# lightspeakers.net
KiCad netlist of a schematic drawn in EAGLE
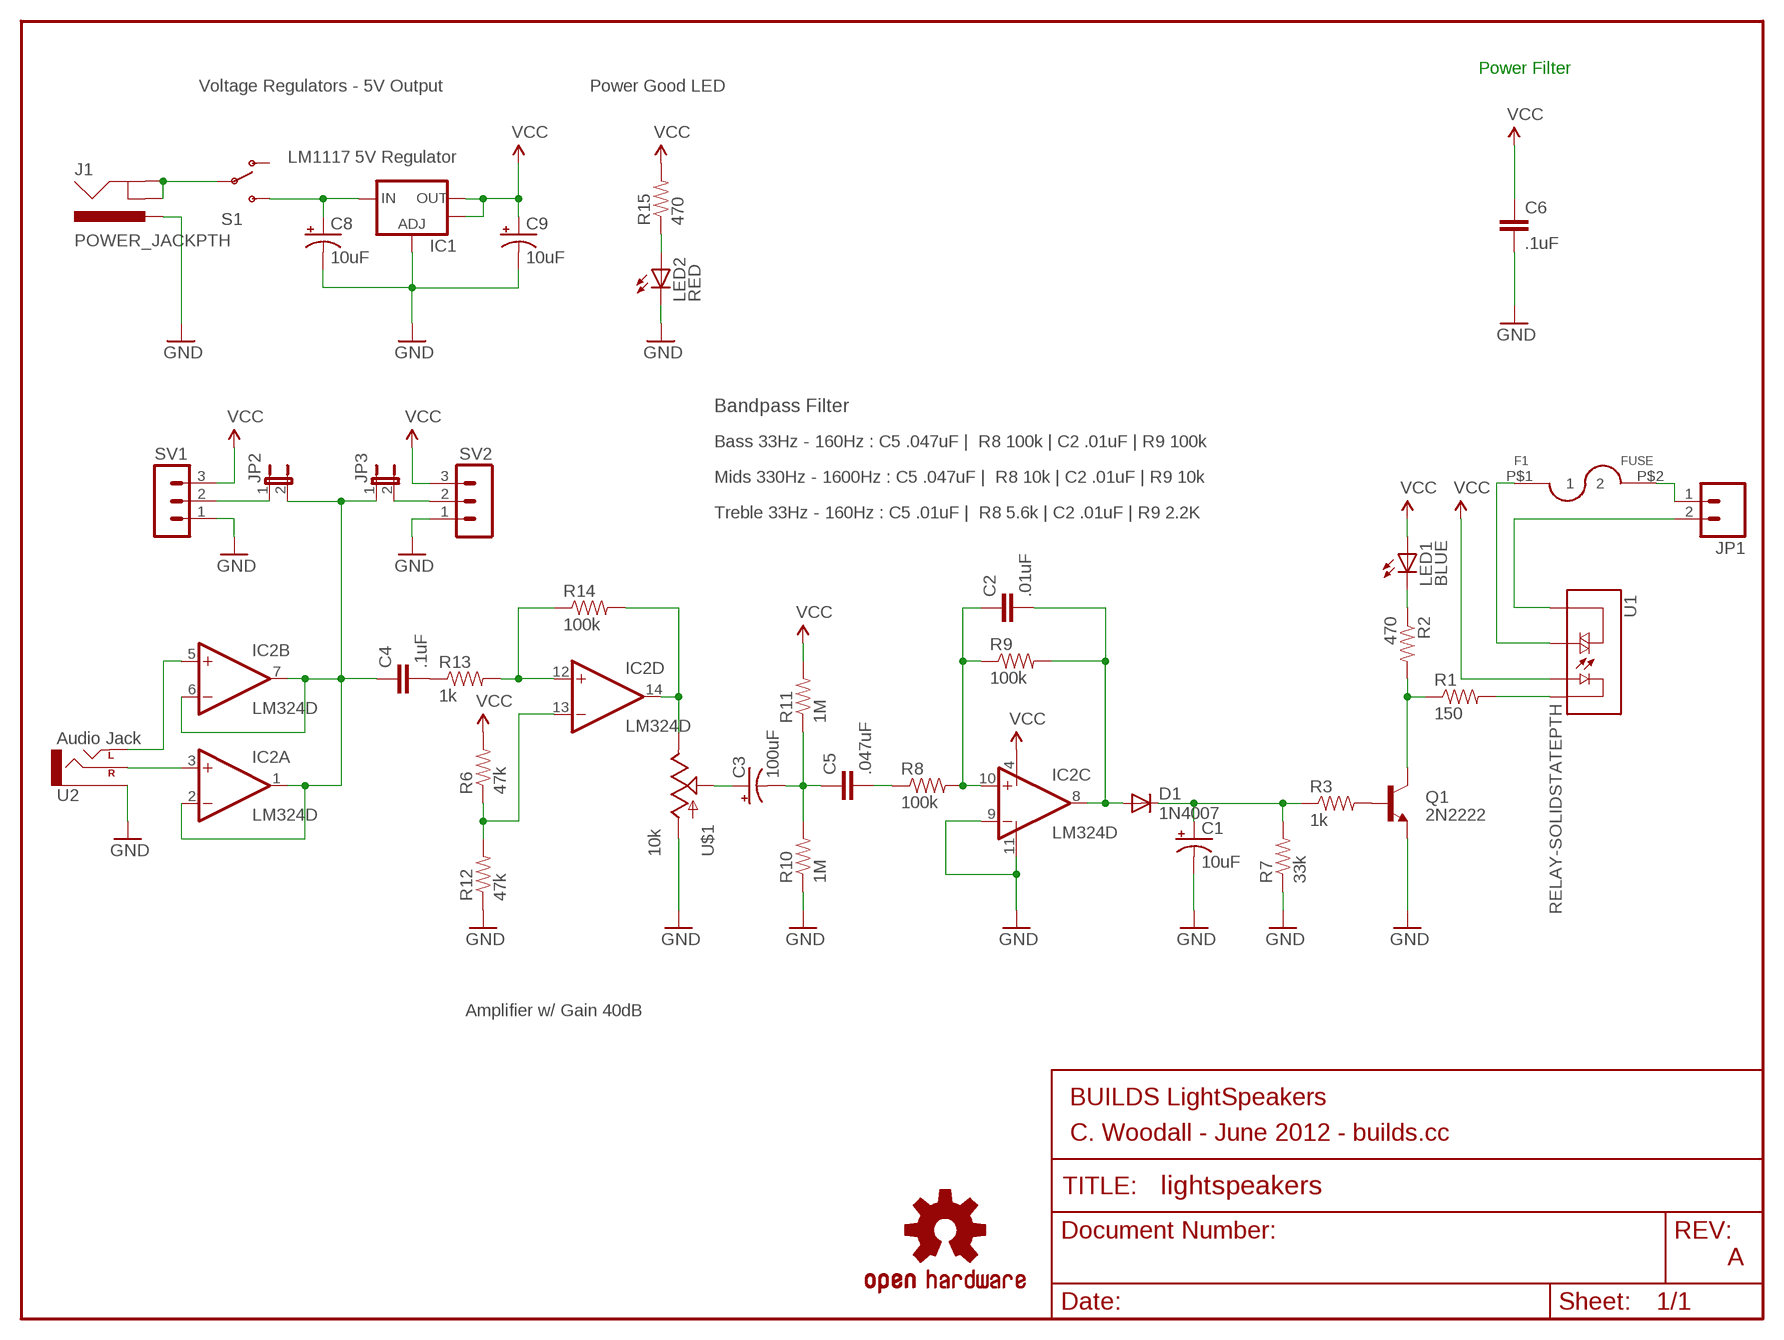
[diagram p0: schematic, sheet 1]

(export (version "E")
  (design (tool "Eeschema 10.0.6"))
  (components
    (comp (ref "C1")
      (value "10uF")
      (footprint "eagle-import:CPOL-RADIAL-10UF-25V")
      (libsource (lib "eagle-import") (part "CAP_POLPTH2"))
    )
    (comp (ref "C2")
      (value ".01uF")
      (footprint "eagle-import:0603-CAP")
      (libsource (lib "eagle-import") (part "CAP0603-CAP"))
    )
    (comp (ref "C3")
      (value "100uF")
      (footprint "eagle-import:CPOL-RADIAL-100UF-25V")
      (libsource (lib "eagle-import") (part "CAP_POLPTH1"))
    )
    (comp (ref "C4")
      (value ".1uF")
      (footprint "eagle-import:0603-CAP")
      (libsource (lib "eagle-import") (part "CAP0603-CAP"))
    )
    (comp (ref "C5")
      (value ".047uF")
      (footprint "eagle-import:0603-CAP")
      (libsource (lib "eagle-import") (part "CAP0603-CAP"))
    )
    (comp (ref "C6")
      (value ".1uF")
      (footprint "eagle-import:0603-CAP")
      (libsource (lib "eagle-import") (part "CAP0603-CAP"))
    )
    (comp (ref "C8")
      (value "10uF")
      (footprint "eagle-import:CPOL-RADIAL-10UF-25V")
      (libsource (lib "eagle-import") (part "CAP_POLPTH2"))
    )
    (comp (ref "C9")
      (value "10uF")
      (footprint "eagle-import:CPOL-RADIAL-10UF-25V")
      (libsource (lib "eagle-import") (part "CAP_POLPTH2"))
    )
    (comp (ref "D1")
      (value "1N4007")
      (footprint "eagle-import:DIODE-1N4001")
      (libsource (lib "eagle-import") (part "DIODEPTH"))
    )
    (comp (ref "F1")
      (value "FUSE")
      (footprint "eagle-import:20MMX5MMFUSE")
      (libsource (lib "eagle-import") (part "FUSE"))
    )
    (comp (ref "IC1")
      (value "LM1117 5V Regulator")
      (footprint "eagle-import:SOT223")
      (libsource (lib "eagle-import") (part "V_REG_LM1117SOT223"))
    )
    (comp (ref "IC2")
      (value "LM324D")
      (footprint "eagle-import:SO14")
      (libsource (lib "eagle-import") (part "LM324D"))
    )
    (comp (ref "J1")
      (value "POWER_JACKPTH")
      (footprint "eagle-import:POWER_JACK_PTH")
      (libsource (lib "eagle-import") (part "POWER_JACKPTH"))
    )
    (comp (ref "JP1")
      (value "M025MM")
      (footprint "eagle-import:SCREWTERMINAL-5MM-2")
      (libsource (lib "eagle-import") (part "M025MM"))
    )
    (comp (ref "JP2")
      (value "JUMPER-2PTH")
      (footprint "eagle-import:1X02")
      (libsource (lib "eagle-import") (part "JUMPER-2PTH"))
    )
    (comp (ref "JP3")
      (value "JUMPER-2PTH")
      (footprint "eagle-import:1X02")
      (libsource (lib "eagle-import") (part "JUMPER-2PTH"))
    )
    (comp (ref "LED1")
      (value "BLUE")
      (footprint "eagle-import:LED-0603")
      (libsource (lib "eagle-import") (part "LED0603"))
    )
    (comp (ref "LED2")
      (value "RED")
      (footprint "eagle-import:LED-0603")
      (libsource (lib "eagle-import") (part "LED0603"))
    )
    (comp (ref "Q1")
      (value "2N2222")
      (footprint "eagle-import:TO-92-AMMO")
      (libsource (lib "eagle-import") (part "TRANSISTOR_NPNTO-92-AMMO"))
    )
    (comp (ref "R1")
      (value "150")
      (footprint "eagle-import:0603-RES")
      (libsource (lib "eagle-import") (part "RESISTOR0603-RES"))
    )
    (comp (ref "R2")
      (value "470")
      (footprint "eagle-import:0603-RES")
      (libsource (lib "eagle-import") (part "RESISTOR0603-RES"))
    )
    (comp (ref "R3")
      (value "1k")
      (footprint "eagle-import:0603-RES")
      (libsource (lib "eagle-import") (part "RESISTOR0603-RES"))
    )
    (comp (ref "R6")
      (value "47k")
      (footprint "eagle-import:0603-RES")
      (libsource (lib "eagle-import") (part "RESISTOR0603-RES"))
    )
    (comp (ref "R7")
      (value "33k")
      (footprint "eagle-import:0603-RES")
      (libsource (lib "eagle-import") (part "RESISTOR0603-RES"))
    )
    (comp (ref "R8")
      (value "100k")
      (footprint "eagle-import:0603-RES")
      (libsource (lib "eagle-import") (part "RESISTOR0603-RES"))
    )
    (comp (ref "R9")
      (value "100k")
      (footprint "eagle-import:0603-RES")
      (libsource (lib "eagle-import") (part "RESISTOR0603-RES"))
    )
    (comp (ref "R10")
      (value "1M")
      (footprint "eagle-import:0603-RES")
      (libsource (lib "eagle-import") (part "RESISTOR0603-RES"))
    )
    (comp (ref "R11")
      (value "1M")
      (footprint "eagle-import:0603-RES")
      (libsource (lib "eagle-import") (part "RESISTOR0603-RES"))
    )
    (comp (ref "R12")
      (value "47k")
      (footprint "eagle-import:0603-RES")
      (libsource (lib "eagle-import") (part "RESISTOR0603-RES"))
    )
    (comp (ref "R13")
      (value "1k")
      (footprint "eagle-import:0603-RES")
      (libsource (lib "eagle-import") (part "RESISTOR0603-RES"))
    )
    (comp (ref "R14")
      (value "100k")
      (footprint "eagle-import:0603-RES")
      (libsource (lib "eagle-import") (part "RESISTOR0603-RES"))
    )
    (comp (ref "R15")
      (value "470")
      (footprint "eagle-import:0603-RES")
      (libsource (lib "eagle-import") (part "RESISTOR0603-RES"))
    )
    (comp (ref "S1")
      (value "SWITCH-SPSTPTH")
      (footprint "eagle-import:SWITCH-SPDT")
      (libsource (lib "eagle-import") (part "SWITCH-SPSTPTH"))
    )
    (comp (ref "SV1")
      (value "MA03-1")
      (footprint "eagle-import:MA03-1")
      (libsource (lib "eagle-import") (part "MA03-1"))
    )
    (comp (ref "SV2")
      (value "MA03-1")
      (footprint "eagle-import:MA03-1")
      (libsource (lib "eagle-import") (part "MA03-1"))
    )
    (comp (ref "U$1")
      (value "10k")
      (footprint "eagle-import:3362U")
      (libsource (lib "eagle-import") (part "POT100K_3362U"))
    )
    (comp (ref "U$2")
      (value "OSHW-LOGOS")
      (footprint "eagle-import:OSHW-LOGO-S")
      (libsource (lib "eagle-import") (part "OSHW-LOGOS"))
    )
    (comp (ref "U1")
      (value "RELAY-SOLIDSTATEPTH")
      (footprint "eagle-import:RELAY-S108T02")
      (libsource (lib "eagle-import") (part "RELAY-SOLIDSTATEPTH"))
    )
    (comp (ref "U2")
      (value "Audio Jack")
      (footprint "eagle-import:AUDIO-JACK")
      (libsource (lib "eagle-import") (part "AUDIO-JACKPTH"))
    )
  )
  (nets
    (net (code "1") (name "GND") (class "Default")
      (node (ref "C1") (pin "2") (pinfunction "-_2") (pintype "passive"))
      (node (ref "C6") (pin "2") (pinfunction "2_2") (pintype "passive"))
      (node (ref "C8") (pin "2") (pinfunction "-_2") (pintype "passive"))
      (node (ref "C9") (pin "2") (pinfunction "-_2") (pintype "passive"))
      (node (ref "IC1") (pin "1") (pinfunction "ADJ_1") (pintype "input"))
      (node (ref "IC2") (pin "11") (pinfunction "V-_11") (pintype "power_in"))
      (node (ref "IC2") (pin "9") (pinfunction "-IN_9") (pintype "input"))
      (node (ref "J1") (pin "PWR") (pinfunction "PWR_PWR") (pintype "bidirectional"))
      (node (ref "LED2") (pin "C") (pinfunction "C_C") (pintype "passive"))
      (node (ref "Q1") (pin "1") (pinfunction "E_1") (pintype "passive"))
      (node (ref "R10") (pin "1") (pinfunction "1_1") (pintype "passive"))
      (node (ref "R12") (pin "1") (pinfunction "1_1") (pintype "passive"))
      (node (ref "R7") (pin "1") (pinfunction "1_1") (pintype "passive"))
      (node (ref "SV1") (pin "1") (pinfunction "1_1") (pintype "passive"))
      (node (ref "SV2") (pin "1") (pinfunction "1_1") (pintype "passive"))
      (node (ref "U$1") (pin "P$3") (pinfunction "A_P$3") (pintype "passive"))
      (node (ref "U2") (pin "SLEEVE") (pinfunction "SLEEVE_SLEEVE") (pintype "bidirectional"))
    )
    (net (code "2") (name "Net-(C1-+)") (class "Default")
      (node (ref "C1") (pin "1") (pinfunction "+_1") (pintype "passive"))
      (node (ref "D1") (pin "C") (pinfunction "C_C") (pintype "passive"))
      (node (ref "R3") (pin "1") (pinfunction "1_1") (pintype "passive"))
      (node (ref "R7") (pin "2") (pinfunction "2_2") (pintype "passive"))
    )
    (net (code "3") (name "Net-(C3-+)") (class "Default")
      (node (ref "C3") (pin "1") (pinfunction "+_1") (pintype "passive"))
      (node (ref "U$1") (pin "P$2") (pinfunction "S_P$2") (pintype "passive"))
    )
    (net (code "4") (name "Net-(C3--)") (class "Default")
      (node (ref "C3") (pin "2") (pinfunction "-_2") (pintype "passive"))
      (node (ref "C5") (pin "1") (pinfunction "1_1") (pintype "passive"))
      (node (ref "R10") (pin "2") (pinfunction "2_2") (pintype "passive"))
      (node (ref "R11") (pin "1") (pinfunction "1_1") (pintype "passive"))
    )
    (net (code "5") (name "Net-(C4-Pad2)") (class "Default")
      (node (ref "C4") (pin "2") (pinfunction "2_2") (pintype "passive"))
      (node (ref "R13") (pin "1") (pinfunction "1_1") (pintype "passive"))
    )
    (net (code "6") (name "Net-(C5-Pad2)") (class "Default")
      (node (ref "C5") (pin "2") (pinfunction "2_2") (pintype "passive"))
      (node (ref "R8") (pin "1") (pinfunction "1_1") (pintype "passive"))
    )
    (net (code "7") (name "Net-(C8-+)") (class "Default")
      (node (ref "C8") (pin "1") (pinfunction "+_1") (pintype "passive"))
      (node (ref "IC1") (pin "3") (pinfunction "IN_3") (pintype "input"))
      (node (ref "S1") (pin "3") (pinfunction "S_3") (pintype "passive"))
    )
    (net (code "8") (name "Net-(F1-1)") (class "Default")
      (node (ref "F1") (pin "P$1") (pinfunction "1_P$1") (pintype "bidirectional"))
      (node (ref "U1") (pin "2") (pinfunction "T2_2") (pintype "bidirectional"))
    )
    (net (code "9") (name "Net-(F1-2)") (class "Default")
      (node (ref "F1") (pin "P$2") (pinfunction "2_P$2") (pintype "bidirectional"))
      (node (ref "JP1") (pin "1") (pinfunction "1_1") (pintype "passive"))
    )
    (net (code "10") (name "Net-(IC2A-+IN)") (class "Default")
      (node (ref "IC2") (pin "3") (pinfunction "+IN_3") (pintype "input"))
      (node (ref "U2") (pin "RING") (pinfunction "RIGHT_RING") (pintype "bidirectional"))
    )
    (net (code "11") (name "Net-(IC2A--IN)") (class "Default")
      (node (ref "C4") (pin "1") (pinfunction "1_1") (pintype "passive"))
      (node (ref "IC2") (pin "1") (pinfunction "OUT_1") (pintype "output"))
      (node (ref "IC2") (pin "2") (pinfunction "-IN_2") (pintype "input"))
      (node (ref "IC2") (pin "6") (pinfunction "-IN_6") (pintype "input"))
      (node (ref "IC2") (pin "7") (pinfunction "OUT_7") (pintype "output"))
      (node (ref "JP2") (pin "2") (pinfunction "2_2") (pintype "passive"))
      (node (ref "JP3") (pin "1") (pinfunction "1_1") (pintype "passive"))
    )
    (net (code "12") (name "Net-(IC2B-+IN)") (class "Default")
      (node (ref "IC2") (pin "5") (pinfunction "+IN_5") (pintype "input"))
      (node (ref "U2") (pin "TIP") (pinfunction "LEFT_TIP") (pintype "bidirectional"))
    )
    (net (code "13") (name "Net-(IC2C-+IN)") (class "Default")
      (node (ref "C2") (pin "1") (pinfunction "1_1") (pintype "passive"))
      (node (ref "IC2") (pin "10") (pinfunction "+IN_10") (pintype "input"))
      (node (ref "R8") (pin "2") (pinfunction "2_2") (pintype "passive"))
      (node (ref "R9") (pin "1") (pinfunction "1_1") (pintype "passive"))
    )
    (net (code "14") (name "Net-(IC2C-OUT)") (class "Default")
      (node (ref "C2") (pin "2") (pinfunction "2_2") (pintype "passive"))
      (node (ref "D1") (pin "A") (pinfunction "A_A") (pintype "passive"))
      (node (ref "IC2") (pin "8") (pinfunction "OUT_8") (pintype "output"))
      (node (ref "R9") (pin "2") (pinfunction "2_2") (pintype "passive"))
    )
    (net (code "15") (name "Net-(IC2D-+IN)") (class "Default")
      (node (ref "IC2") (pin "12") (pinfunction "+IN_12") (pintype "input"))
      (node (ref "R13") (pin "2") (pinfunction "2_2") (pintype "passive"))
      (node (ref "R14") (pin "1") (pinfunction "1_1") (pintype "passive"))
    )
    (net (code "16") (name "Net-(IC2D--IN)") (class "Default")
      (node (ref "IC2") (pin "13") (pinfunction "-IN_13") (pintype "input"))
      (node (ref "R12") (pin "2") (pinfunction "2_2") (pintype "passive"))
      (node (ref "R6") (pin "1") (pinfunction "1_1") (pintype "passive"))
    )
    (net (code "17") (name "Net-(IC2D-OUT)") (class "Default")
      (node (ref "IC2") (pin "14") (pinfunction "OUT_14") (pintype "output"))
      (node (ref "R14") (pin "2") (pinfunction "2_2") (pintype "passive"))
      (node (ref "U$1") (pin "P$1") (pinfunction "E_P$1") (pintype "passive"))
    )
    (net (code "18") (name "Net-(JP2-Pad1)") (class "Default")
      (node (ref "JP2") (pin "1") (pinfunction "1_1") (pintype "passive"))
      (node (ref "SV1") (pin "2") (pinfunction "2_2") (pintype "passive"))
    )
    (net (code "19") (name "Net-(JP3-Pad2)") (class "Default")
      (node (ref "JP3") (pin "2") (pinfunction "2_2") (pintype "passive"))
      (node (ref "SV2") (pin "2") (pinfunction "2_2") (pintype "passive"))
    )
    (net (code "20") (name "Net-(LED1-PadC)") (class "Default")
      (node (ref "LED1") (pin "C") (pinfunction "C_C") (pintype "passive"))
      (node (ref "R2") (pin "1") (pinfunction "1_1") (pintype "passive"))
    )
    (net (code "21") (name "Net-(LED2-PadA)") (class "Default")
      (node (ref "LED2") (pin "A") (pinfunction "A_A") (pintype "passive"))
      (node (ref "R15") (pin "1") (pinfunction "1_1") (pintype "passive"))
    )
    (net (code "22") (name "Net-(Q1-B)") (class "Default")
      (node (ref "Q1") (pin "2") (pinfunction "B_2") (pintype "passive"))
      (node (ref "R3") (pin "2") (pinfunction "2_2") (pintype "passive"))
    )
    (net (code "23") (name "Net-(Q1-C)") (class "Default")
      (node (ref "Q1") (pin "3") (pinfunction "C_3") (pintype "passive"))
      (node (ref "R1") (pin "1") (pinfunction "1_1") (pintype "passive"))
      (node (ref "R2") (pin "2") (pinfunction "2_2") (pintype "passive"))
    )
    (net (code "24") (name "Net-(S1-P)") (class "Default")
      (node (ref "J1") (pin "GND") (pinfunction "GND_GND") (pintype "bidirectional"))
      (node (ref "J1") (pin "GNDBREAK") (pinfunction "GNDBREAK_GNDBREAK") (pintype "bidirectional"))
      (node (ref "S1") (pin "2") (pinfunction "P_2") (pintype "passive"))
    )
    (net (code "25") (name "Net-(U1--)") (class "Default")
      (node (ref "R1") (pin "2") (pinfunction "2_2") (pintype "passive"))
      (node (ref "U1") (pin "4") (pinfunction "-_4") (pintype "bidirectional"))
    )
    (net (code "26") (name "Net-(U1-T1)") (class "Default")
      (node (ref "JP1") (pin "2") (pinfunction "2_2") (pintype "passive"))
      (node (ref "U1") (pin "1") (pinfunction "T1_1") (pintype "bidirectional"))
    )
    (net (code "27") (name "VCC") (class "Default")
      (node (ref "C6") (pin "1") (pinfunction "1_1") (pintype "passive"))
      (node (ref "C9") (pin "1") (pinfunction "+_1") (pintype "passive"))
      (node (ref "IC1") (pin "2") (pinfunction "OUT_2") (pintype "output"))
      (node (ref "IC1") (pin "4") (pinfunction "OUT_4") (pintype "output"))
      (node (ref "IC2") (pin "4") (pinfunction "V+_4") (pintype "power_in"))
      (node (ref "LED1") (pin "A") (pinfunction "A_A") (pintype "passive"))
      (node (ref "R11") (pin "2") (pinfunction "2_2") (pintype "passive"))
      (node (ref "R15") (pin "2") (pinfunction "2_2") (pintype "passive"))
      (node (ref "R6") (pin "2") (pinfunction "2_2") (pintype "passive"))
      (node (ref "SV1") (pin "3") (pinfunction "3_3") (pintype "passive"))
      (node (ref "SV2") (pin "3") (pinfunction "3_3") (pintype "passive"))
      (node (ref "U1") (pin "3") (pinfunction "+_3") (pintype "bidirectional"))
    )
    (net (code "28") (name "unconnected-(S1-O-Pad1)") (class "Default")
      (node (ref "S1") (pin "1") (pinfunction "O_1") (pintype "passive"))
    )
  )
)
